# Power_MCU.net
KiCad netlist of a schematic drawn in Altium Designer
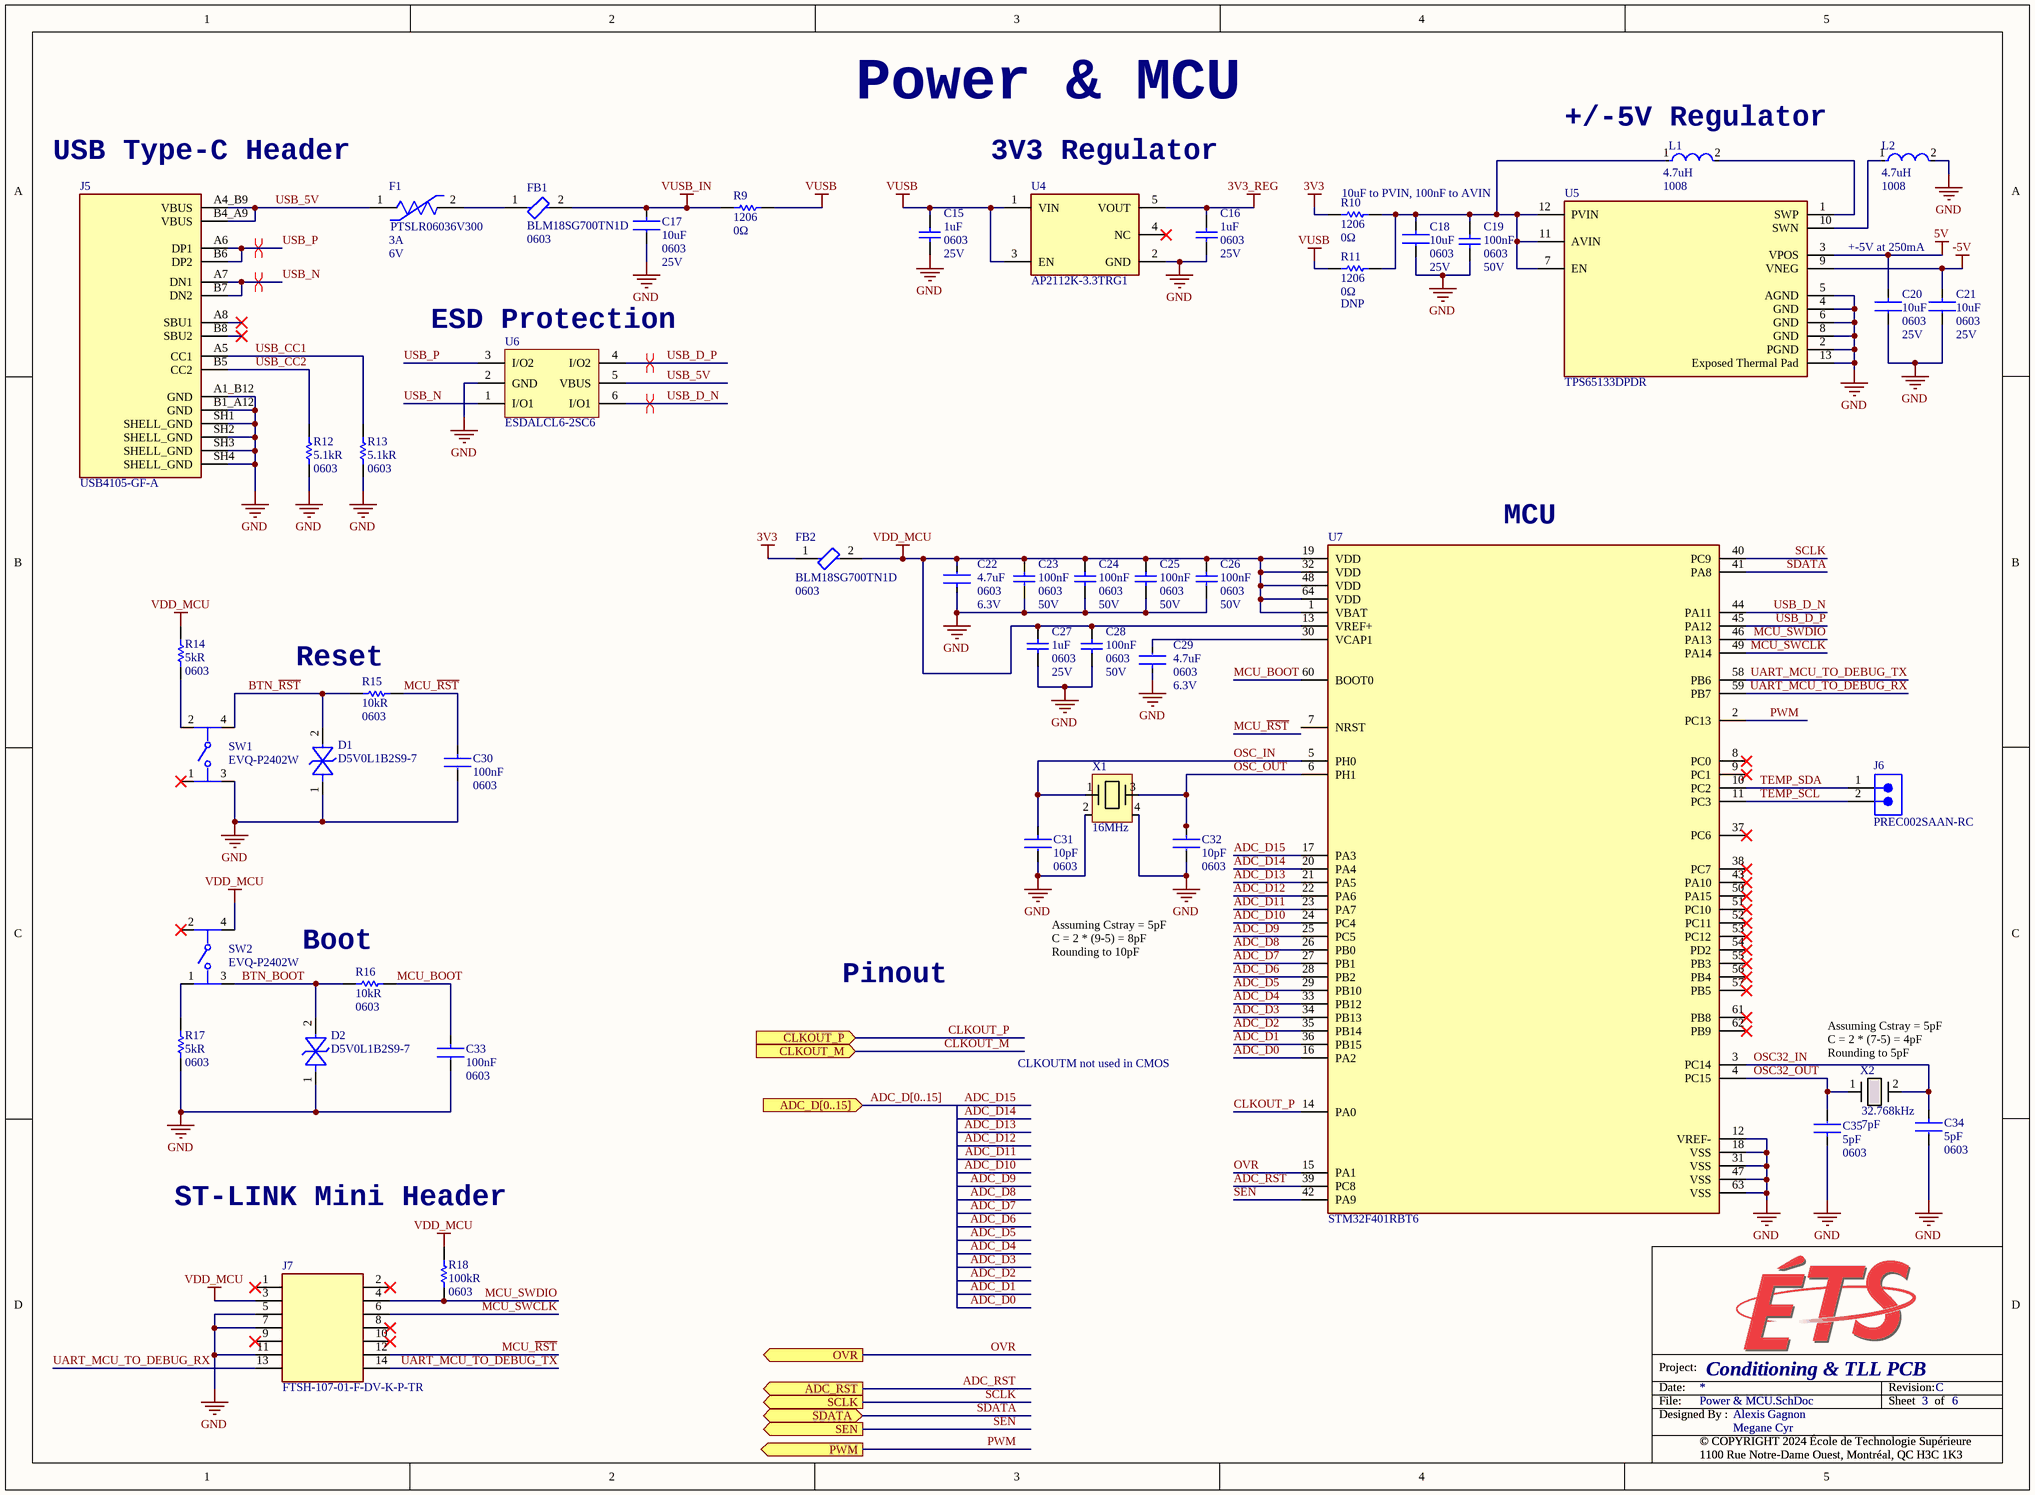
[diagram p0: Power & MCU.SchDoc]

(export (version "E")
  (design (tool "Eeschema 10.0.6"))
  (components
    (comp (ref "C15")
      (value "1uF")
      (footprint "ANTC1608X90N")
      (description "CAP CER 1UF 25V X5R 0603")
      (fields
        (field (name "MANUFACTURER") "Samsung")
        (field (name "MANUFACTURER PART NUMBER") "CL10A105KA8NNNC")
        (field (name "CASE/PACKAGE") "0603")
        (field (name "RATED DC VOLTAGE (URDC)") "25V")
      )
      (libsource (lib "ETS_Library") (part "CL10A105KA8NNNC"))
    )
    (comp (ref "C16")
      (value "1uF")
      (footprint "ANTC1608X90N")
      (description "CAP CER 1UF 25V X5R 0603")
      (fields
        (field (name "MANUFACTURER") "Samsung")
        (field (name "MANUFACTURER PART NUMBER") "CL10A105KA8NNNC")
        (field (name "CASE/PACKAGE") "0603")
        (field (name "RATED DC VOLTAGE (URDC)") "25V")
      )
      (libsource (lib "ETS_Library") (part "CL10A105KA8NNNC"))
    )
    (comp (ref "C17")
      (value "10uF")
      (footprint "BMS:C0603")
      (description "CAP CER 10UF 25V X5R 0603")
      (fields
        (field (name "TOLERANCE") "20%")
        (field (name "MANUFACTURER") "Murata")
        (field (name "CASE/PACKAGE") "0603")
        (field (name "VOLTAGE") "25V")
      )
      (libsource (lib "BMS") (part "GRM188R61E106MA73D"))
    )
    (comp (ref "C18")
      (value "10uF")
      (footprint "BMS:C0603")
      (description "CAP CER 10UF 25V X5R 0603")
      (fields
        (field (name "TOLERANCE") "20%")
        (field (name "MANUFACTURER") "Murata")
        (field (name "CASE/PACKAGE") "0603")
        (field (name "VOLTAGE") "25V")
      )
      (libsource (lib "BMS") (part "GRM188R61E106MA73D"))
    )
    (comp (ref "C19")
      (value "100nF")
      (footprint "ANTC1608X90N")
      (description "CAP CER 0.1UF 50V X7R 0603")
      (fields
        (field (name "MANUFACTURER") "Samsung")
        (field (name "MANUFACTURER PART NUMBER") "CL10B104KB8NNWC")
        (field (name "CASE/PACKAGE") "0603")
        (field (name "VOLTAGE RATING") "50V")
      )
      (libsource (lib "ETS_Library") (part "CL10B104KB8NNWC"))
    )
    (comp (ref "C20")
      (value "10uF")
      (footprint "BMS:C0603")
      (description "CAP CER 10UF 25V X5R 0603")
      (fields
        (field (name "TOLERANCE") "20%")
        (field (name "MANUFACTURER") "Murata")
        (field (name "CASE/PACKAGE") "0603")
        (field (name "VOLTAGE") "25V")
      )
      (libsource (lib "BMS") (part "GRM188R61E106MA73D"))
    )
    (comp (ref "C21")
      (value "10uF")
      (footprint "BMS:C0603")
      (description "CAP CER 10UF 25V X5R 0603")
      (fields
        (field (name "TOLERANCE") "20%")
        (field (name "MANUFACTURER") "Murata")
        (field (name "CASE/PACKAGE") "0603")
        (field (name "VOLTAGE") "25V")
      )
      (libsource (lib "BMS") (part "GRM188R61E106MA73D"))
    )
    (comp (ref "C22")
      (value "4.7uF")
      (footprint "FP-C0603-CG-IPC_B")
      (description "CAP CER 4.7UF 6.3V X5R 0603")
      (fields
        (field (name "PACKAGE") "0603")
        (field (name "TOLERANCE") "10%")
        (field (name "MANUFACTURER") "Kemet")
        (field (name "VOLTAGE RATING") "6.3V")
      )
      (libsource (lib "ETS_Library") (part "CMP-2006-02256-2"))
    )
    (comp (ref "C23")
      (value "100nF")
      (footprint "ANTC1608X90N")
      (description "CAP CER 0.1UF 50V X7R 0603")
      (fields
        (field (name "MANUFACTURER") "Samsung")
        (field (name "MANUFACTURER PART NUMBER") "CL10B104KB8NNWC")
        (field (name "CASE/PACKAGE") "0603")
        (field (name "VOLTAGE RATING") "50V")
      )
      (libsource (lib "ETS_Library") (part "CL10B104KB8NNWC"))
    )
    (comp (ref "C24")
      (value "100nF")
      (footprint "ANTC1608X90N")
      (description "CAP CER 0.1UF 50V X7R 0603")
      (fields
        (field (name "MANUFACTURER") "Samsung")
        (field (name "MANUFACTURER PART NUMBER") "CL10B104KB8NNWC")
        (field (name "CASE/PACKAGE") "0603")
        (field (name "VOLTAGE RATING") "50V")
      )
      (libsource (lib "ETS_Library") (part "CL10B104KB8NNWC"))
    )
    (comp (ref "C25")
      (value "100nF")
      (footprint "ANTC1608X90N")
      (description "CAP CER 0.1UF 50V X7R 0603")
      (fields
        (field (name "MANUFACTURER") "Samsung")
        (field (name "MANUFACTURER PART NUMBER") "CL10B104KB8NNWC")
        (field (name "CASE/PACKAGE") "0603")
        (field (name "VOLTAGE RATING") "50V")
      )
      (libsource (lib "ETS_Library") (part "CL10B104KB8NNWC"))
    )
    (comp (ref "C26")
      (value "100nF")
      (footprint "ANTC1608X90N")
      (description "CAP CER 0.1UF 50V X7R 0603")
      (fields
        (field (name "MANUFACTURER") "Samsung")
        (field (name "MANUFACTURER PART NUMBER") "CL10B104KB8NNWC")
        (field (name "CASE/PACKAGE") "0603")
        (field (name "VOLTAGE RATING") "50V")
      )
      (libsource (lib "ETS_Library") (part "CL10B104KB8NNWC"))
    )
    (comp (ref "C27")
      (value "1uF")
      (footprint "ANTC1608X90N")
      (description "CAP CER 1UF 25V X5R 0603")
      (fields
        (field (name "MANUFACTURER") "Samsung")
        (field (name "MANUFACTURER PART NUMBER") "CL10A105KA8NNNC")
        (field (name "CASE/PACKAGE") "0603")
        (field (name "RATED DC VOLTAGE (URDC)") "25V")
      )
      (libsource (lib "ETS_Library") (part "CL10A105KA8NNNC"))
    )
    (comp (ref "C28")
      (value "100nF")
      (footprint "ANTC1608X90N")
      (description "CAP CER 0.1UF 50V X7R 0603")
      (fields
        (field (name "MANUFACTURER") "Samsung")
        (field (name "MANUFACTURER PART NUMBER") "CL10B104KB8NNWC")
        (field (name "CASE/PACKAGE") "0603")
        (field (name "VOLTAGE RATING") "50V")
      )
      (libsource (lib "ETS_Library") (part "CL10B104KB8NNWC"))
    )
    (comp (ref "C29")
      (value "4.7uF")
      (footprint "FP-C0603-CG-IPC_B")
      (description "CAP CER 4.7UF 6.3V X5R 0603")
      (fields
        (field (name "PACKAGE") "0603")
        (field (name "TOLERANCE") "10%")
        (field (name "MANUFACTURER") "Kemet")
        (field (name "VOLTAGE RATING") "6.3V")
      )
      (libsource (lib "ETS_Library") (part "CMP-2006-02256-2"))
    )
    (comp (ref "C30")
      (value "100nF")
      (footprint "BMS:C0603-V2")
      (description "CAP CER 100NF 100V X8L 0603")
      (fields
        (field (name "MANUFACTURER") "Samsung")
        (field (name "MANUFACTURER PART NUMBER") "CL10E104KC8VPNC")
        (field (name "CASE") "0603")
      )
      (libsource (lib "BMS") (part "CL10E104KC8VPNC"))
    )
    (comp (ref "C31")
      (value "10pF")
      (footprint "BMS:C0603-V2")
      (description "CAP CER 10PF 100V C0G/NP0 0603")
      (fields
        (field (name "MANUFACTURER") "Murata")
        (field (name "MANUFACTURER PART NUMBER") "GCM1885C2A100JA16D")
        (field (name "CASE/PACKAGE") "0603")
      )
      (libsource (lib "BMS") (part "GCM1885C2A100JA16D"))
    )
    (comp (ref "C32")
      (value "10pF")
      (footprint "BMS:C0603-V2")
      (description "CAP CER 10PF 100V C0G/NP0 0603")
      (fields
        (field (name "MANUFACTURER") "Murata")
        (field (name "MANUFACTURER PART NUMBER") "GCM1885C2A100JA16D")
        (field (name "CASE/PACKAGE") "0603")
      )
      (libsource (lib "BMS") (part "GCM1885C2A100JA16D"))
    )
    (comp (ref "C33")
      (value "100nF")
      (footprint "BMS:C0603-V2")
      (description "CAP CER 100NF 100V X8L 0603")
      (fields
        (field (name "MANUFACTURER") "Samsung")
        (field (name "MANUFACTURER PART NUMBER") "CL10E104KC8VPNC")
        (field (name "CASE") "0603")
      )
      (libsource (lib "BMS") (part "CL10E104KC8VPNC"))
    )
    (comp (ref "C34")
      (value "5pF")
      (footprint "C0603-V2")
      (description "CAP CER 5PF 100V C0G/NP0 0603")
      (fields
        (field (name "MANUFACTURER") "Walsin Technologies")
        (field (name "MANUFACTURER PART NUMBER") "0603N5R0B101CT")
        (field (name "CASE") "0603")
      )
      (libsource (lib "BMS") (part "0603N5R0B101CT"))
    )
    (comp (ref "C35")
      (value "5pF")
      (footprint "C0603-V2")
      (description "CAP CER 5PF 100V C0G/NP0 0603")
      (fields
        (field (name "MANUFACTURER") "Walsin Technologies")
        (field (name "MANUFACTURER PART NUMBER") "0603N5R0B101CT")
        (field (name "CASE") "0603")
      )
      (libsource (lib "BMS") (part "0603N5R0B101CT"))
    )
    (comp (ref "D1")
      (value "D5V0L1B2S9-7")
      (footprint "SOD923_DIO")
      (description "TVS DIODE 5VWM 14VC SOD923")
      (fields (field (name "MANUFACTURER") "Diodes"))
      (libsource (lib "BMS") (part "D5V0L1B2S9-7"))
    )
    (comp (ref "D2")
      (value "D5V0L1B2S9-7")
      (footprint "SOD923_DIO")
      (description "TVS DIODE 5VWM 14VC SOD923")
      (fields (field (name "MANUFACTURER") "Diodes"))
      (libsource (lib "BMS") (part "D5V0L1B2S9-7"))
    )
    (comp (ref "F1")
      (value "PTSLR06036V300")
      (footprint "BMS:FP-PTSLR06036V300-MFG")
      (description "PTC RESET FUSE 3A 6V 0603")
      (fields
        (field (name "MANUFACTURER") "Eaton")
        (field (name "CURRENT HOLD") "3A")
        (field (name "VOLTAGE") "6V")
      )
      (libsource (lib "BMS") (part "PTSLR06036V300"))
    )
    (comp (ref "FB1")
      (value "BLM18SG700TN1D")
      (footprint "BMS:BLM18SG700TN1D-MFG")
      (description "FERRITE BEAD 70 OHM 0603 1LN")
      (fields
        (field (name "TOLERANCE") "25%")
        (field (name "MANUFACTURER") "Murata")
        (field (name "CASE CODE (IMPERIAL)") "0603")
      )
      (libsource (lib "BMS") (part "BLM18SG700TN1D"))
    )
    (comp (ref "FB2")
      (value "BLM18SG700TN1D")
      (footprint "BMS:BLM18SG700TN1D-MFG")
      (description "FERRITE BEAD 70 OHM 0603 1LN")
      (fields
        (field (name "TOLERANCE") "25%")
        (field (name "MANUFACTURER") "Murata")
        (field (name "CASE CODE (IMPERIAL)") "0603")
      )
      (libsource (lib "BMS") (part "BLM18SG700TN1D"))
    )
    (comp (ref "J5")
      (value "USB4105-GF-A")
      (footprint "BMS:GCT_USB4105-GF-A")
      (description "CONN RCP USB2.0 TYP C 24P SMD RA")
      (fields (field (name "MANUFACTURER") "Global Connector Technology"))
      (libsource (lib "BMS") (part "USB4105-GF-A"))
    )
    (comp (ref "J6")
      (value "PREC002SAAN-RC")
      (footprint "CONN_PREC002SAAN-RC_SUL")
      (description "CONN HEADER .100 SNGL STR 2POS")
      (fields (field (name "MANUFACTURER") "Sullins"))
      (libsource (lib "ETS_Library") (part "PREC002SAAN-RC"))
    )
    (comp (ref "J7")
      (value "FTSH-107-01-F-DV-K-P-TR")
      (footprint "BMS:SAMTEC_FTSH-107-01-F-DV-K-P-TR")
      (description "CONN HEADER SMD 14POS 1.27MM")
      (fields (field (name "MANUFACTURER") "Samtec"))
      (libsource (lib "BMS") (part "FTSH-107-01-F-DV-K-P-TR"))
    )
    (comp (ref "L1")
      (value "1239AS-H-4R7M=P2")
      (footprint "FP-DFE252012C-MFG")
      (description "Shielded Wirewound Inductor 4.7uH 20% 1300mA 0.24Ω 1008 (2520)")
      (fields
        (field (name "CASE/PACKAGE") "1008")
        (field (name "INDUCTANCE") "4.7uH")
        (field (name "TOLERANCE") "20%")
      )
      (libsource (lib "ETS_Library") (part "1239AS-H-4R7M=P2"))
    )
    (comp (ref "L2")
      (value "1239AS-H-4R7M=P2")
      (footprint "FP-DFE252012C-MFG")
      (description "Shielded Wirewound Inductor 4.7uH 20% 1300mA 0.24Ω 1008 (2520)")
      (fields
        (field (name "CASE/PACKAGE") "1008")
        (field (name "INDUCTANCE") "4.7uH")
        (field (name "TOLERANCE") "20%")
      )
      (libsource (lib "ETS_Library") (part "1239AS-H-4R7M=P2"))
    )
    (comp (ref "R9")
      (value "RC1206JR-070RL")
      (footprint "BMS:R1206")
      (description "RES 0 OHM JUMPER 1/4W 1206")
      (fields
        (field (name "MANUFACTURER") "YAGEO")
        (field (name "OCTOPART") "https://octopart.com/rc1206jr-070rl-yageo-40025601")
        (field (name "CASE/PACKAGE") "1206")
        (field (name "RESISTANCE") "0Ω")
      )
      (libsource (lib "BMS") (part "RC1206JR-070RL"))
    )
    (comp (ref "R10")
      (value "RC1206JR-070RL")
      (footprint "BMS:R1206")
      (description "RES 0 OHM JUMPER 1/4W 1206")
      (fields
        (field (name "MANUFACTURER") "YAGEO")
        (field (name "OCTOPART") "https://octopart.com/rc1206jr-070rl-yageo-40025601")
        (field (name "CASE/PACKAGE") "1206")
        (field (name "RESISTANCE") "0Ω")
      )
      (libsource (lib "BMS") (part "RC1206JR-070RL"))
    )
    (comp (ref "R11")
      (value "RC1206JR-070RL")
      (footprint "BMS:R1206")
      (description "RES 0 OHM JUMPER 1/4W 1206")
      (fields
        (field (name "MANUFACTURER") "YAGEO")
        (field (name "OCTOPART") "https://octopart.com/rc1206jr-070rl-yageo-40025601")
        (field (name "CASE/PACKAGE") "1206")
        (field (name "RESISTANCE") "0Ω")
      )
      (libsource (lib "BMS") (part "RC1206JR-070RL"))
    )
    (comp (ref "R12")
      (value "5.1kR")
      (footprint "BMS:R0603")
      (description "RES 5.1K OHM 1% 1/10W 0603")
      (fields
        (field (name "MANUFACTURER") "Yageo")
        (field (name "PART NUMBER") "RC0603FR-075K1L")
        (field (name "CASE/PACKAGE") "0603")
      )
      (libsource (lib "BMS") (part "RC0603FR-075K1L"))
    )
    (comp (ref "R13")
      (value "5.1kR")
      (footprint "BMS:R0603")
      (description "RES 5.1K OHM 1% 1/10W 0603")
      (fields
        (field (name "MANUFACTURER") "Yageo")
        (field (name "PART NUMBER") "RC0603FR-075K1L")
        (field (name "CASE/PACKAGE") "0603")
      )
      (libsource (lib "BMS") (part "RC0603FR-075K1L"))
    )
    (comp (ref "R14")
      (value "5kR")
      (footprint "BMS:R0603")
      (description "RES 5K OHM 0.1% 1/10W 0603")
      (fields
        (field (name "MANUFACTURER") "Yageo")
        (field (name "MANUFACTURER PART NUMBER") "RT0603BRE075KL")
        (field (name "CASE") "0603")
      )
      (libsource (lib "BMS") (part "RT0603BRE075KL"))
    )
    (comp (ref "R15")
      (value "10kR")
      (footprint "BMS:R0603")
      (description "10 kOhms ±1% 0.1W, 1/10W Chip Resistor 0603 (1608 Metric) Moisture Resistant Thick Film")
      (fields
        (field (name "MANUFACTURER") "Yageo")
        (field (name "MANUFACTURER PART NUMBER") "RC0603FR-0710KL")
        (field (name "CASE/PACKAGE") "0603")
      )
      (libsource (lib "BMS") (part "RC0603FR-0710KL"))
    )
    (comp (ref "R16")
      (value "10kR")
      (footprint "BMS:R0603")
      (description "10 kOhms ±1% 0.1W, 1/10W Chip Resistor 0603 (1608 Metric) Moisture Resistant Thick Film")
      (fields
        (field (name "MANUFACTURER") "Yageo")
        (field (name "MANUFACTURER PART NUMBER") "RC0603FR-0710KL")
        (field (name "CASE/PACKAGE") "0603")
      )
      (libsource (lib "BMS") (part "RC0603FR-0710KL"))
    )
    (comp (ref "R17")
      (value "5kR")
      (footprint "BMS:R0603")
      (description "RES 5K OHM 0.1% 1/10W 0603")
      (fields
        (field (name "MANUFACTURER") "Yageo")
        (field (name "MANUFACTURER PART NUMBER") "RT0603BRE075KL")
        (field (name "CASE") "0603")
      )
      (libsource (lib "BMS") (part "RT0603BRE075KL"))
    )
    (comp (ref "R18")
      (value "100kR")
      (footprint "BMS:R0603")
      (description "RES 100K OHM 1% 1/10W 0603")
      (fields
        (field (name "MANUFACTURER") "Yageo")
        (field (name "MANUFACTURER PART NUMBER") "RC0603FR-07100KL")
        (field (name "CASE/PACKAGE") "0603")
      )
      (libsource (lib "BMS") (part "RC0603FR-07100KL"))
    )
    (comp (ref "SW1")
      (value "EVQ-P2402W")
      (footprint "FP-EVQ-P2402W-MFG")
      (description "SWITCH TACTILE SPST-NO 0.02A 15V")
      (fields (field (name "MANUFACTURER") "Panasonic"))
      (libsource (lib "BMS") (part "EVQ-P2402W"))
    )
    (comp (ref "SW2")
      (value "EVQ-P2402W")
      (footprint "FP-EVQ-P2402W-MFG")
      (description "SWITCH TACTILE SPST-NO 0.02A 15V")
      (fields (field (name "MANUFACTURER") "Panasonic"))
      (libsource (lib "BMS") (part "EVQ-P2402W"))
    )
    (comp (ref "U4")
      (value "AP2112K-3.3TRG1")
      (footprint "FP-SOT25-MFG")
      (description "IC REG LINEAR 3.3V 600MA SOT25")
      (libsource (lib "ETS_Library") (part "AP2112K-3.3TRG1"))
    )
    (comp (ref "U5")
      (value "TPS65133DPDR")
      (footprint "FP-DPD0012A-MFG")
      (description "IC REG AMOLED DISPL 2OUT 12WSON")
      (libsource (lib "ETS_Library") (part "TPS65133DPDR"))
    )
    (comp (ref "U6")
      (value "ESDALCL6-2SC6")
      (footprint "BMS:ESDALCL6-2SC6")
      (description "TVS DIODE 3VWM 17VC SOT23-6")
      (fields (field (name "MANUFACTURER") "STMicroelectronics"))
      (libsource (lib "BMS") (part "ESDALCL6-2SC6"))
    )
    (comp (ref "U7")
      (value "STM32F401RBT6")
      (footprint "QFP50P1200X1200X160-64N")
      (fields (field (name "MF") "STMicroelectronics"))
      (libsource (lib "ETS_Library") (part "STM32F401RBT6"))
    )
    (comp (ref "X1")
      (value "16MHz")
      (footprint "FP-TSX-3225-MFG")
      (description "CRYSTAL 16.0000MHZ 9PF SMD")
      (fields
        (field (name "MANUFACTURER") "Epson")
        (field (name "MANUFACTURER PART NUMBER") "TSX-3225 16.0000MF18X-AC0")
      )
      (libsource (lib "BMS") (part "TSX-3225 16.0000MF18X-AC0"))
    )
    (comp (ref "X2")
      (value "32.768kHz")
      (footprint "XTAL_SC32S-7PF20PPM_EPS")
      (description "CRYSTAL 32.7680KHZ 7PF SMD")
      (fields
        (field (name "MANUFACTURER") "Seiko")
        (field (name "MANUFACTURER PART NUMBER") "SC32S-7PF20PPM")
        (field (name "LOAD CAPACITANCE") "7pF")
      )
      (libsource (lib "BMS") (part "SC32S-7PF20PPM"))
    )
  )
  (nets
    (net (code "1") (name "-5V") (class "Default")
      (node (ref "C21") (pin "1") (pinfunction "1_1") (pintype "passive"))
      (node (ref "U5") (pin "9") (pinfunction "VNEG_9") (pintype "passive"))
    )
    (net (code "2") (name "/ADC_D0") (class "Default")
      (node (ref "U7") (pin "16") (pinfunction "PA2_16") (pintype "passive"))
    )
    (net (code "3") (name "/ADC_D1") (class "Default")
      (node (ref "U7") (pin "36") (pinfunction "PB15_36") (pintype "passive"))
    )
    (net (code "4") (name "/ADC_D2") (class "Default")
      (node (ref "U7") (pin "35") (pinfunction "PB14_35") (pintype "passive"))
    )
    (net (code "5") (name "/ADC_D3") (class "Default")
      (node (ref "U7") (pin "34") (pinfunction "PB13_34") (pintype "passive"))
    )
    (net (code "6") (name "/ADC_D4") (class "Default")
      (node (ref "U7") (pin "33") (pinfunction "PB12_33") (pintype "passive"))
    )
    (net (code "7") (name "/ADC_D5") (class "Default")
      (node (ref "U7") (pin "29") (pinfunction "PB10_29") (pintype "passive"))
    )
    (net (code "8") (name "/ADC_D6") (class "Default")
      (node (ref "U7") (pin "28") (pinfunction "PB2_28") (pintype "passive"))
    )
    (net (code "9") (name "/ADC_D7") (class "Default")
      (node (ref "U7") (pin "27") (pinfunction "PB1_27") (pintype "passive"))
    )
    (net (code "10") (name "/ADC_D8") (class "Default")
      (node (ref "U7") (pin "26") (pinfunction "PB0_26") (pintype "passive"))
    )
    (net (code "11") (name "/ADC_D9") (class "Default")
      (node (ref "U7") (pin "25") (pinfunction "PC5_25") (pintype "passive"))
    )
    (net (code "12") (name "/ADC_D10") (class "Default")
      (node (ref "U7") (pin "24") (pinfunction "PC4_24") (pintype "passive"))
    )
    (net (code "13") (name "/ADC_D11") (class "Default")
      (node (ref "U7") (pin "23") (pinfunction "PA7_23") (pintype "passive"))
    )
    (net (code "14") (name "/ADC_D12") (class "Default")
      (node (ref "U7") (pin "22") (pinfunction "PA6_22") (pintype "passive"))
    )
    (net (code "15") (name "/ADC_D13") (class "Default")
      (node (ref "U7") (pin "21") (pinfunction "PA5_21") (pintype "passive"))
    )
    (net (code "16") (name "/ADC_D14") (class "Default")
      (node (ref "U7") (pin "20") (pinfunction "PA4_20") (pintype "passive"))
    )
    (net (code "17") (name "/ADC_D15") (class "Default")
      (node (ref "U7") (pin "17") (pinfunction "PA3_17") (pintype "passive"))
    )
    (net (code "19") (name "/ADC_RST") (class "Default")
      (node (ref "U7") (pin "39") (pinfunction "PC8_39") (pintype "passive"))
    )
    (net (code "20") (name "/BTN_BOOT") (class "Default")
      (node (ref "D2") (pin "2") (pinfunction "2_2") (pintype "passive"))
      (node (ref "R16") (pin "1") (pinfunction "1_1") (pintype "passive"))
      (node (ref "SW2") (pin "3") (pinfunction "3_3") (pintype "passive"))
    )
    (net (code "21") (name "/BTN_~{RST}") (class "Default")
      (node (ref "D1") (pin "2") (pinfunction "2_2") (pintype "passive"))
      (node (ref "R15") (pin "1") (pinfunction "1_1") (pintype "passive"))
      (node (ref "SW1") (pin "4") (pinfunction "4_4") (pintype "passive"))
    )
    (net (code "23") (name "/CLKOUT_P") (class "Default")
      (node (ref "U7") (pin "14") (pinfunction "PA0_14") (pintype "passive"))
    )
    (net (code "24") (name "/MCU_BOOT") (class "Default")
      (node (ref "C33") (pin "1") (pinfunction "1_1") (pintype "passive"))
      (node (ref "R16") (pin "2") (pinfunction "2_2") (pintype "passive"))
      (node (ref "U7") (pin "60") (pinfunction "BOOT0_60") (pintype "passive"))
    )
    (net (code "25") (name "/MCU_SWCLK") (class "Default")
      (node (ref "J7") (pin "6") (pinfunction "6_6") (pintype "passive"))
      (node (ref "U7") (pin "49") (pinfunction "PA14_49") (pintype "passive"))
    )
    (net (code "26") (name "/MCU_SWDIO") (class "Default")
      (node (ref "J7") (pin "4") (pinfunction "4_4") (pintype "passive"))
      (node (ref "R18") (pin "1") (pinfunction "1_1") (pintype "passive"))
      (node (ref "U7") (pin "46") (pinfunction "PA13_46") (pintype "passive"))
    )
    (net (code "27") (name "/MCU_~{RST}") (class "Default")
      (node (ref "C30") (pin "1") (pinfunction "1_1") (pintype "passive"))
      (node (ref "J7") (pin "12") (pinfunction "12_12") (pintype "passive"))
      (node (ref "R15") (pin "2") (pinfunction "2_2") (pintype "passive"))
    )
    (net (code "28") (name "/OSC32_IN") (class "Default")
      (node (ref "C34") (pin "1") (pinfunction "1_1") (pintype "passive"))
      (node (ref "U7") (pin "3") (pinfunction "PC14_3") (pintype "passive"))
      (node (ref "X2") (pin "2") (pinfunction "2_2") (pintype "passive"))
    )
    (net (code "29") (name "/OSC32_OUT") (class "Default")
      (node (ref "C35") (pin "2") (pinfunction "2_2") (pintype "passive"))
      (node (ref "U7") (pin "4") (pinfunction "PC15_4") (pintype "passive"))
      (node (ref "X2") (pin "1") (pinfunction "1_1") (pintype "passive"))
    )
    (net (code "30") (name "/OSC_IN") (class "Default")
      (node (ref "C31") (pin "1") (pinfunction "1_1") (pintype "passive"))
      (node (ref "U7") (pin "5") (pinfunction "PH0_5") (pintype "passive"))
      (node (ref "X1") (pin "1") (pinfunction "1_1") (pintype "passive"))
    )
    (net (code "31") (name "/OSC_OUT") (class "Default")
      (node (ref "C32") (pin "1") (pinfunction "1_1") (pintype "passive"))
      (node (ref "U7") (pin "6") (pinfunction "PH1_6") (pintype "passive"))
      (node (ref "X1") (pin "3") (pinfunction "3_3") (pintype "passive"))
    )
    (net (code "32") (name "/OVR") (class "Default")
      (node (ref "U7") (pin "15") (pinfunction "PA1_15") (pintype "passive"))
    )
    (net (code "33") (name "/PWM") (class "Default")
      (node (ref "U7") (pin "2") (pinfunction "PC13_2") (pintype "passive"))
    )
    (net (code "34") (name "/SCLK") (class "Default")
      (node (ref "U7") (pin "40") (pinfunction "PC9_40") (pintype "passive"))
    )
    (net (code "35") (name "/SDATA") (class "Default")
      (node (ref "U7") (pin "41") (pinfunction "PA8_41") (pintype "passive"))
    )
    (net (code "36") (name "/SEN") (class "Default")
      (node (ref "U7") (pin "42") (pinfunction "PA9_42") (pintype "passive"))
    )
    (net (code "37") (name "/TEMP_SCL") (class "Default")
      (node (ref "J6") (pin "2") (pinfunction "2_2") (pintype "passive"))
      (node (ref "U7") (pin "11") (pinfunction "PC3_11") (pintype "passive"))
    )
    (net (code "38") (name "/TEMP_SDA") (class "Default")
      (node (ref "J6") (pin "1") (pinfunction "1_1") (pintype "passive"))
      (node (ref "U7") (pin "10") (pinfunction "PC2_10") (pintype "passive"))
    )
    (net (code "39") (name "/UART_MCU_TO_DEBUG_RX") (class "Default")
      (node (ref "J7") (pin "13") (pinfunction "13_13") (pintype "passive"))
      (node (ref "U7") (pin "59") (pinfunction "PB7_59") (pintype "passive"))
    )
    (net (code "40") (name "/UART_MCU_TO_DEBUG_TX") (class "Default")
      (node (ref "J7") (pin "14") (pinfunction "14_14") (pintype "passive"))
      (node (ref "U7") (pin "58") (pinfunction "PB6_58") (pintype "passive"))
    )
    (net (code "41") (name "/USB_5V") (class "Default")
      (node (ref "F1") (pin "1") (pinfunction "1_1") (pintype "passive"))
      (node (ref "J5") (pin "A4_B9") (pinfunction "VBUS_A4_B9") (pintype "passive"))
      (node (ref "J5") (pin "B4_A9") (pinfunction "VBUS_B4_A9") (pintype "passive"))
      (node (ref "U6") (pin "5") (pinfunction "VBUS_5") (pintype "passive"))
    )
    (net (code "42") (name "/USB_CC1") (class "Default")
      (node (ref "J5") (pin "A5") (pinfunction "CC1_A5") (pintype "passive"))
      (node (ref "R13") (pin "2") (pinfunction "2_2") (pintype "passive"))
    )
    (net (code "43") (name "/USB_CC2") (class "Default")
      (node (ref "J5") (pin "B5") (pinfunction "CC2_B5") (pintype "passive"))
      (node (ref "R12") (pin "2") (pinfunction "2_2") (pintype "passive"))
    )
    (net (code "44") (name "/USB_D_N") (class "Default")
      (node (ref "U6") (pin "6") (pinfunction "I/O1_6") (pintype "passive"))
      (node (ref "U7") (pin "44") (pinfunction "PA11_44") (pintype "passive"))
    )
    (net (code "45") (name "/USB_D_P") (class "Default")
      (node (ref "U6") (pin "4") (pinfunction "I/O2_4") (pintype "passive"))
      (node (ref "U7") (pin "45") (pinfunction "PA12_45") (pintype "passive"))
    )
    (net (code "46") (name "/USB_N") (class "Default")
      (node (ref "J5") (pin "A7") (pinfunction "DN1_A7") (pintype "passive"))
      (node (ref "J5") (pin "B7") (pinfunction "DN2_B7") (pintype "passive"))
      (node (ref "U6") (pin "1") (pinfunction "I/O1_1") (pintype "passive"))
    )
    (net (code "47") (name "/USB_P") (class "Default")
      (node (ref "J5") (pin "A6") (pinfunction "DP1_A6") (pintype "passive"))
      (node (ref "J5") (pin "B6") (pinfunction "DP2_B6") (pintype "passive"))
      (node (ref "U6") (pin "3") (pinfunction "I/O2_3") (pintype "passive"))
    )
    (net (code "48") (name "3V3") (class "Default")
      (node (ref "FB2") (pin "1") (pinfunction "1_1") (pintype "passive"))
      (node (ref "R10") (pin "1") (pinfunction "1_1") (pintype "passive"))
    )
    (net (code "49") (name "3V3_REG") (class "Default")
      (node (ref "C16") (pin "2") (pinfunction "2_2") (pintype "passive"))
      (node (ref "U4") (pin "5") (pinfunction "VOUT_5") (pintype "power_in"))
    )
    (net (code "50") (name "5V") (class "Default")
      (node (ref "C20") (pin "1") (pinfunction "1_1") (pintype "passive"))
      (node (ref "U5") (pin "3") (pinfunction "VPOS_3") (pintype "passive"))
    )
    (net (code "51") (name "GND") (class "Default")
      (node (ref "C15") (pin "1") (pinfunction "1_1") (pintype "passive"))
      (node (ref "C16") (pin "1") (pinfunction "1_1") (pintype "passive"))
      (node (ref "C17") (pin "2") (pinfunction "2_2") (pintype "passive"))
      (node (ref "C18") (pin "2") (pinfunction "2_2") (pintype "passive"))
      (node (ref "C19") (pin "2") (pinfunction "2_2") (pintype "passive"))
      (node (ref "C20") (pin "2") (pinfunction "2_2") (pintype "passive"))
      (node (ref "C21") (pin "2") (pinfunction "2_2") (pintype "passive"))
      (node (ref "C22") (pin "1") (pinfunction "1_1") (pintype "passive"))
      (node (ref "C23") (pin "2") (pinfunction "2_2") (pintype "passive"))
      (node (ref "C24") (pin "2") (pinfunction "2_2") (pintype "passive"))
      (node (ref "C25") (pin "2") (pinfunction "2_2") (pintype "passive"))
      (node (ref "C26") (pin "2") (pinfunction "2_2") (pintype "passive"))
      (node (ref "C27") (pin "1") (pinfunction "1_1") (pintype "passive"))
      (node (ref "C28") (pin "2") (pinfunction "2_2") (pintype "passive"))
      (node (ref "C29") (pin "1") (pinfunction "1_1") (pintype "passive"))
      (node (ref "C30") (pin "2") (pinfunction "2_2") (pintype "passive"))
      (node (ref "C31") (pin "2") (pinfunction "2_2") (pintype "passive"))
      (node (ref "C32") (pin "2") (pinfunction "2_2") (pintype "passive"))
      (node (ref "C33") (pin "2") (pinfunction "2_2") (pintype "passive"))
      (node (ref "C34") (pin "2") (pinfunction "2_2") (pintype "passive"))
      (node (ref "C35") (pin "1") (pinfunction "1_1") (pintype "passive"))
      (node (ref "D1") (pin "1") (pinfunction "1_1") (pintype "passive"))
      (node (ref "D2") (pin "1") (pinfunction "1_1") (pintype "passive"))
      (node (ref "J5") (pin "A1_B12") (pinfunction "GND_A1_B12") (pintype "passive"))
      (node (ref "J5") (pin "B1_A12") (pinfunction "GND_B1_A12") (pintype "passive"))
      (node (ref "J5") (pin "SH1") (pinfunction "SHELL_GND_SH1") (pintype "passive"))
      (node (ref "J5") (pin "SH2") (pinfunction "SHELL_GND_SH2") (pintype "passive"))
      (node (ref "J5") (pin "SH3") (pinfunction "SHELL_GND_SH3") (pintype "passive"))
      (node (ref "J5") (pin "SH4") (pinfunction "SHELL_GND_SH4") (pintype "passive"))
      (node (ref "J7") (pin "11") (pinfunction "11_11") (pintype "passive"))
      (node (ref "J7") (pin "5") (pinfunction "5_5") (pintype "passive"))
      (node (ref "J7") (pin "7") (pinfunction "7_7") (pintype "passive"))
      (node (ref "L2") (pin "2") (pinfunction "2_2") (pintype "passive"))
      (node (ref "R12") (pin "1") (pinfunction "1_1") (pintype "passive"))
      (node (ref "R13") (pin "1") (pinfunction "1_1") (pintype "passive"))
      (node (ref "R17") (pin "1") (pinfunction "1_1") (pintype "passive"))
      (node (ref "SW1") (pin "3") (pinfunction "3_3") (pintype "passive"))
      (node (ref "U4") (pin "2") (pinfunction "GND_2") (pintype "power_in"))
      (node (ref "U5") (pin "13") (pinfunction "Exposed_Thermal_Pad_13") (pintype "passive"))
      (node (ref "U5") (pin "2") (pinfunction "PGND_2") (pintype "passive"))
      (node (ref "U5") (pin "4") (pinfunction "GND_4") (pintype "passive"))
      (node (ref "U5") (pin "5") (pinfunction "AGND_5") (pintype "passive"))
      (node (ref "U5") (pin "6") (pinfunction "GND_6") (pintype "passive"))
      (node (ref "U5") (pin "8") (pinfunction "GND_8") (pintype "passive"))
      (node (ref "U6") (pin "2") (pinfunction "GND_2") (pintype "passive"))
      (node (ref "U7") (pin "12") (pinfunction "VREF-_12") (pintype "passive"))
      (node (ref "U7") (pin "18") (pinfunction "VSS_18") (pintype "passive"))
      (node (ref "U7") (pin "31") (pinfunction "VSS_31") (pintype "passive"))
      (node (ref "U7") (pin "47") (pinfunction "VSS_47") (pintype "passive"))
      (node (ref "U7") (pin "63") (pinfunction "VSS_63") (pintype "passive"))
      (node (ref "X1") (pin "2") (pinfunction "2_2") (pintype "passive"))
      (node (ref "X1") (pin "4") (pinfunction "4_4") (pintype "passive"))
    )
    (net (code "52") (name "Net-(F1-Pad2)") (class "Default")
      (node (ref "F1") (pin "2") (pinfunction "2_2") (pintype "passive"))
      (node (ref "FB1") (pin "1") (pinfunction "1_1") (pintype "passive"))
    )
    (net (code "53") (name "Net-(R14-Pad1)") (class "Default")
      (node (ref "R14") (pin "1") (pinfunction "1_1") (pintype "passive"))
      (node (ref "SW1") (pin "2") (pinfunction "2_2") (pintype "passive"))
    )
    (net (code "54") (name "Net-(R17-Pad2)") (class "Default")
      (node (ref "R17") (pin "2") (pinfunction "2_2") (pintype "passive"))
      (node (ref "SW2") (pin "1") (pinfunction "1_1") (pintype "passive"))
    )
    (net (code "55") (name "Net-(U5-AVIN)") (class "Default")
      (node (ref "C18") (pin "1") (pinfunction "1_1") (pintype "passive"))
      (node (ref "C19") (pin "1") (pinfunction "1_1") (pintype "passive"))
      (node (ref "L1") (pin "1") (pinfunction "1_1") (pintype "passive"))
      (node (ref "R10") (pin "2") (pinfunction "2_2") (pintype "passive"))
      (node (ref "R11") (pin "2") (pinfunction "2_2") (pintype "passive"))
      (node (ref "U5") (pin "11") (pinfunction "AVIN_11") (pintype "passive"))
      (node (ref "U5") (pin "12") (pinfunction "PVIN_12") (pintype "passive"))
      (node (ref "U5") (pin "7") (pinfunction "EN_7") (pintype "passive"))
    )
    (net (code "56") (name "Net-(U5-SWN)") (class "Default")
      (node (ref "L2") (pin "1") (pinfunction "1_1") (pintype "passive"))
      (node (ref "U5") (pin "10") (pinfunction "SWN_10") (pintype "passive"))
    )
    (net (code "57") (name "Net-(U5-SWP)") (class "Default")
      (node (ref "L1") (pin "2") (pinfunction "2_2") (pintype "passive"))
      (node (ref "U5") (pin "1") (pinfunction "SWP_1") (pintype "passive"))
    )
    (net (code "58") (name "Net-(U7-VCAP1)") (class "Default")
      (node (ref "C29") (pin "2") (pinfunction "2_2") (pintype "passive"))
      (node (ref "U7") (pin "30") (pinfunction "VCAP1_30") (pintype "passive"))
    )
    (net (code "59") (name "VDD_MCU") (class "Default")
      (node (ref "C22") (pin "2") (pinfunction "2_2") (pintype "passive"))
      (node (ref "C23") (pin "1") (pinfunction "1_1") (pintype "passive"))
      (node (ref "C24") (pin "1") (pinfunction "1_1") (pintype "passive"))
      (node (ref "C25") (pin "1") (pinfunction "1_1") (pintype "passive"))
      (node (ref "C26") (pin "1") (pinfunction "1_1") (pintype "passive"))
      (node (ref "C27") (pin "2") (pinfunction "2_2") (pintype "passive"))
      (node (ref "C28") (pin "1") (pinfunction "1_1") (pintype "passive"))
      (node (ref "FB2") (pin "2") (pinfunction "2_2") (pintype "passive"))
      (node (ref "J7") (pin "3") (pinfunction "3_3") (pintype "passive"))
      (node (ref "R14") (pin "2") (pinfunction "2_2") (pintype "passive"))
      (node (ref "R18") (pin "2") (pinfunction "2_2") (pintype "passive"))
      (node (ref "SW2") (pin "4") (pinfunction "4_4") (pintype "passive"))
      (node (ref "U7") (pin "1") (pinfunction "VBAT_1") (pintype "passive"))
      (node (ref "U7") (pin "13") (pinfunction "VREF+_13") (pintype "passive"))
      (node (ref "U7") (pin "19") (pinfunction "VDD_19") (pintype "passive"))
      (node (ref "U7") (pin "32") (pinfunction "VDD_32") (pintype "passive"))
      (node (ref "U7") (pin "48") (pinfunction "VDD_48") (pintype "passive"))
      (node (ref "U7") (pin "64") (pinfunction "VDD_64") (pintype "passive"))
    )
    (net (code "60") (name "VUSB") (class "Default")
      (node (ref "C15") (pin "2") (pinfunction "2_2") (pintype "passive"))
      (node (ref "R11") (pin "1") (pinfunction "1_1") (pintype "passive"))
      (node (ref "R9") (pin "2") (pinfunction "2_2") (pintype "passive"))
      (node (ref "U4") (pin "1") (pinfunction "VIN_1") (pintype "power_in"))
      (node (ref "U4") (pin "3") (pinfunction "EN_3") (pintype "passive"))
    )
    (net (code "61") (name "VUSB_IN") (class "Default")
      (node (ref "C17") (pin "1") (pinfunction "1_1") (pintype "passive"))
      (node (ref "FB1") (pin "2") (pinfunction "2_2") (pintype "passive"))
      (node (ref "R9") (pin "1") (pinfunction "1_1") (pintype "passive"))
    )
    (net (code "62") (name "unconnected-(J5-SBU1-PadA8)") (class "Default")
      (node (ref "J5") (pin "A8") (pinfunction "SBU1_A8") (pintype "passive+no_connect"))
    )
    (net (code "63") (name "unconnected-(J5-SBU2-PadB8)") (class "Default")
      (node (ref "J5") (pin "B8") (pinfunction "SBU2_B8") (pintype "passive+no_connect"))
    )
    (net (code "64") (name "unconnected-(J7-Pad1)") (class "Default")
      (node (ref "J7") (pin "1") (pinfunction "1_1") (pintype "passive+no_connect"))
    )
    (net (code "65") (name "unconnected-(J7-Pad2)") (class "Default")
      (node (ref "J7") (pin "2") (pinfunction "2_2") (pintype "passive+no_connect"))
    )
    (net (code "66") (name "unconnected-(J7-Pad8)") (class "Default")
      (node (ref "J7") (pin "8") (pinfunction "8_8") (pintype "passive+no_connect"))
    )
    (net (code "67") (name "unconnected-(J7-Pad9)") (class "Default")
      (node (ref "J7") (pin "9") (pinfunction "9_9") (pintype "passive+no_connect"))
    )
    (net (code "68") (name "unconnected-(J7-Pad10)") (class "Default")
      (node (ref "J7") (pin "10") (pinfunction "10_10") (pintype "passive+no_connect"))
    )
    (net (code "69") (name "unconnected-(SW1-Pad1)") (class "Default")
      (node (ref "SW1") (pin "1") (pinfunction "1_1") (pintype "passive+no_connect"))
    )
    (net (code "70") (name "unconnected-(SW2-Pad2)") (class "Default")
      (node (ref "SW2") (pin "2") (pinfunction "2_2") (pintype "passive+no_connect"))
    )
    (net (code "71") (name "unconnected-(U4-NC-Pad4)") (class "Default")
      (node (ref "U4") (pin "4") (pinfunction "NC_4") (pintype "passive+no_connect"))
    )
    (net (code "72") (name "unconnected-(U7-NRST-Pad7)") (class "Default")
      (node (ref "U7") (pin "7") (pinfunction "NRST_7") (pintype "passive"))
    )
    (net (code "73") (name "unconnected-(U7-PA10-Pad43)") (class "Default")
      (node (ref "U7") (pin "43") (pinfunction "PA10_43") (pintype "passive+no_connect"))
    )
    (net (code "74") (name "unconnected-(U7-PA15-Pad50)") (class "Default")
      (node (ref "U7") (pin "50") (pinfunction "PA15_50") (pintype "passive+no_connect"))
    )
    (net (code "75") (name "unconnected-(U7-PB3-Pad55)") (class "Default")
      (node (ref "U7") (pin "55") (pinfunction "PB3_55") (pintype "passive+no_connect"))
    )
    (net (code "76") (name "unconnected-(U7-PB4-Pad56)") (class "Default")
      (node (ref "U7") (pin "56") (pinfunction "PB4_56") (pintype "passive+no_connect"))
    )
    (net (code "77") (name "unconnected-(U7-PB5-Pad57)") (class "Default")
      (node (ref "U7") (pin "57") (pinfunction "PB5_57") (pintype "passive+no_connect"))
    )
    (net (code "78") (name "unconnected-(U7-PB8-Pad61)") (class "Default")
      (node (ref "U7") (pin "61") (pinfunction "PB8_61") (pintype "passive+no_connect"))
    )
    (net (code "79") (name "unconnected-(U7-PB9-Pad62)") (class "Default")
      (node (ref "U7") (pin "62") (pinfunction "PB9_62") (pintype "passive+no_connect"))
    )
    (net (code "80") (name "unconnected-(U7-PC0-Pad8)") (class "Default")
      (node (ref "U7") (pin "8") (pinfunction "PC0_8") (pintype "passive+no_connect"))
    )
    (net (code "81") (name "unconnected-(U7-PC1-Pad9)") (class "Default")
      (node (ref "U7") (pin "9") (pinfunction "PC1_9") (pintype "passive+no_connect"))
    )
    (net (code "82") (name "unconnected-(U7-PC6-Pad37)") (class "Default")
      (node (ref "U7") (pin "37") (pinfunction "PC6_37") (pintype "passive+no_connect"))
    )
    (net (code "83") (name "unconnected-(U7-PC7-Pad38)") (class "Default")
      (node (ref "U7") (pin "38") (pinfunction "PC7_38") (pintype "passive+no_connect"))
    )
    (net (code "84") (name "unconnected-(U7-PC10-Pad51)") (class "Default")
      (node (ref "U7") (pin "51") (pinfunction "PC10_51") (pintype "passive+no_connect"))
    )
    (net (code "85") (name "unconnected-(U7-PC11-Pad52)") (class "Default")
      (node (ref "U7") (pin "52") (pinfunction "PC11_52") (pintype "passive+no_connect"))
    )
    (net (code "86") (name "unconnected-(U7-PC12-Pad53)") (class "Default")
      (node (ref "U7") (pin "53") (pinfunction "PC12_53") (pintype "passive+no_connect"))
    )
    (net (code "87") (name "unconnected-(U7-PD2-Pad54)") (class "Default")
      (node (ref "U7") (pin "54") (pinfunction "PD2_54") (pintype "passive+no_connect"))
    )
  )
)
